# ch340-usb-serial.net
KiCad netlist of a schematic drawn in Altium Designer
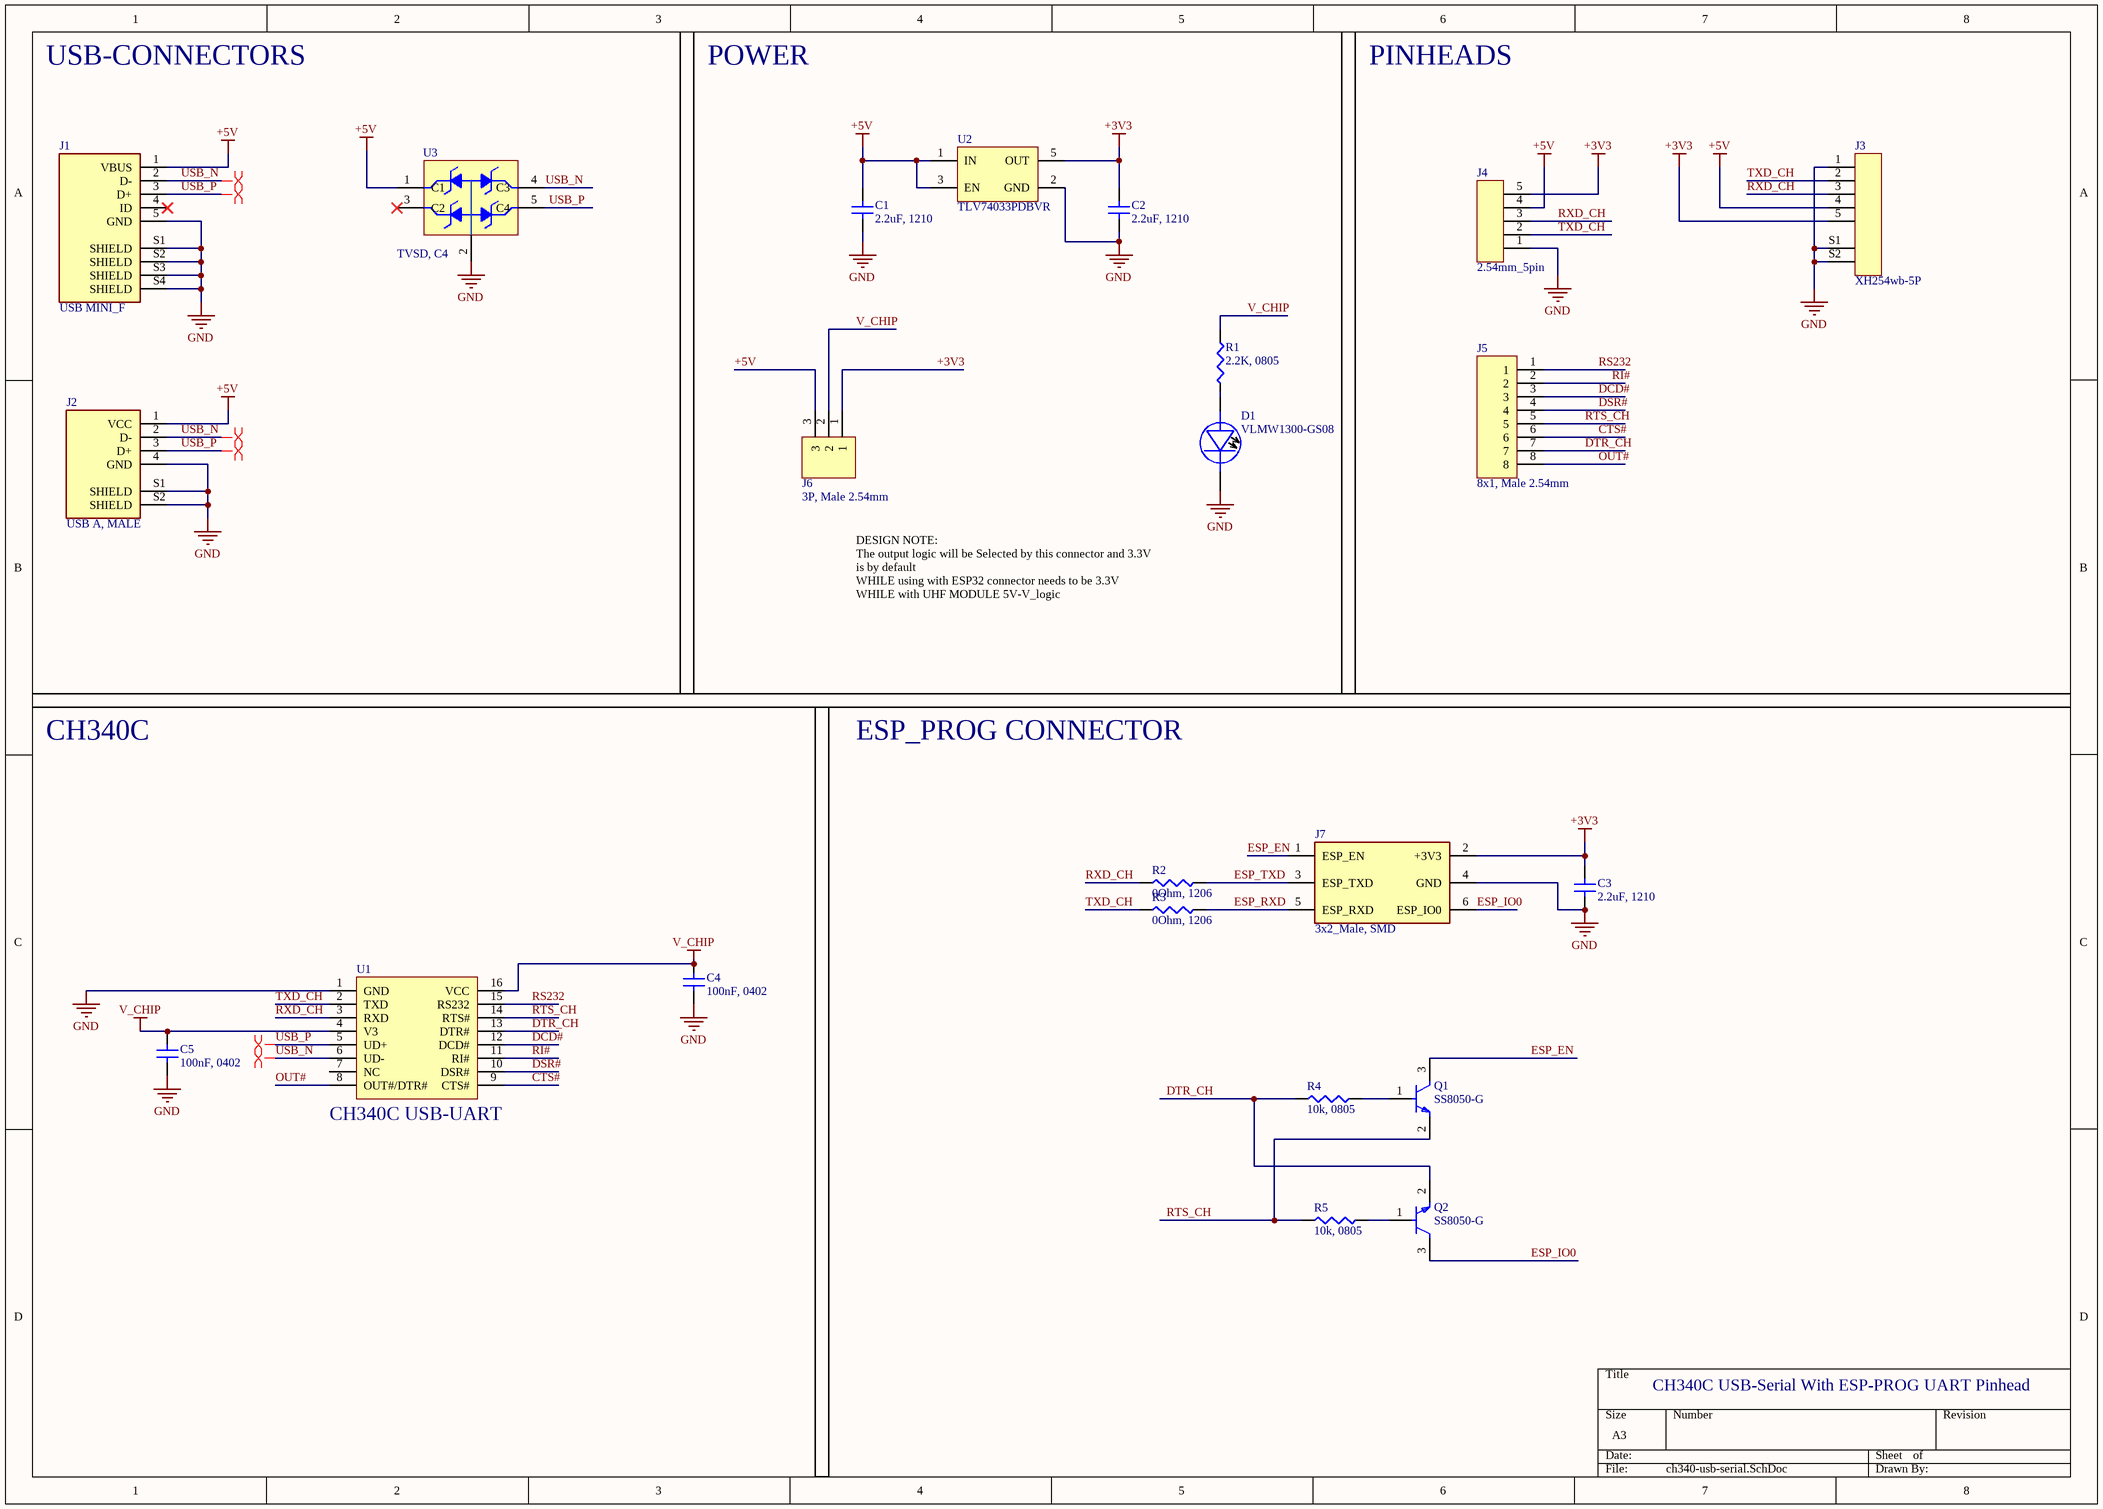
[diagram p0: ch340-usb-serial.SchDoc]

(export (version "E")
  (design (tool "Eeschema 10.0.6"))
  (components
    (comp (ref "C1")
      (value "2.2uF, 1210")
      (footprint "CAP_1210")
      (description "CAP CER 2.2UF 100V X7R 1210")
      (fields
        (field (name "MANUFACTURER") "Samsung")
        (field (name "MANUFACTURER PART NUMBER") "CL32B225KCJSNNE")
      )
      (libsource (lib "Schlib") (part "CL32B225KCJSNNE"))
    )
    (comp (ref "C2")
      (value "2.2uF, 1210")
      (footprint "CAP_1210")
      (description "CAP CER 2.2UF 100V X7R 1210")
      (fields
        (field (name "MANUFACTURER") "Samsung")
        (field (name "MANUFACTURER PART NUMBER") "CL32B225KCJSNNE")
      )
      (libsource (lib "Schlib") (part "CL32B225KCJSNNE"))
    )
    (comp (ref "C3")
      (value "2.2uF, 1210")
      (footprint "CAP_1210")
      (description "CAP CER 2.2UF 100V X7R 1210")
      (fields
        (field (name "MANUFACTURER") "Samsung")
        (field (name "MANUFACTURER PART NUMBER") "CL32B225KCJSNNE")
      )
      (libsource (lib "Schlib") (part "CL32B225KCJSNNE"))
    )
    (comp (ref "C4")
      (value "100nF, 0402")
      (footprint "CAP_0402")
      (description "0.1 µF ±10% 50V Ceramic Capacitor X7R 0402 (1005 Metric)")
      (fields
        (field (name "MANUFACTURER") "Samsung")
        (field (name "MANUFACTURER PART NUMBER") "CL05B104KB54PNC")
      )
      (libsource (lib "Schlib") (part "CL05B104KB54PNC"))
    )
    (comp (ref "C5")
      (value "100nF, 0402")
      (footprint "CAP_0402")
      (description "0.1 µF ±10% 50V Ceramic Capacitor X7R 0402 (1005 Metric)")
      (fields
        (field (name "MANUFACTURER") "Samsung")
        (field (name "MANUFACTURER PART NUMBER") "CL05B104KB54PNC")
      )
      (libsource (lib "Schlib") (part "CL05B104KB54PNC"))
    )
    (comp (ref "D1")
      (value "VLMW1300-GS08")
      (footprint "LED_0603")
      (description "LED COOL WHITE 0603 SMD")
      (fields (field (name "MANUFACTURER") "Vishay Semiconductors"))
      (libsource (lib "Schlib") (part "VLMW1300-GS08"))
    )
    (comp (ref "J1")
      (value "USB MINI_F")
      (footprint "USB_B_Female")
      (description "MINI USB B TYPE RECEPTACLE 5POS")
      (fields
        (field (name "MANUFACTURER") "Amphenol")
        (field (name "MANUFACTURER PART NUMBER") "GMSB0532112YEU")
      )
      (libsource (lib "Schlib") (part "GMSB0532112YEU"))
    )
    (comp (ref "J2")
      (value "USB A, MALE")
      (footprint "USB_A_MALE")
      (description "CONN PLUG USB2.0 TYPEA 4P SMD RA")
      (fields (field (name "MANUFACTURER") "Molex") (field (name "MANUFACTURER PART NUMBER") "0480372200"))
      (libsource (lib "Schlib") (part "0480372200"))
    )
    (comp (ref "J3")
      (value "XH254wb-5P")
      (footprint "5PIN_Header_Connectotor")
      (description "SMT SMD Horizontal Socket Male Header Connector")
      (libsource (lib "Schlib") (part "XH254wb-5P"))
    )
    (comp (ref "J4")
      (value "2.54mm_5pin")
      (footprint "5x1P_Male_2.54")
      (description "CONN HEADER VERT 5POS 2.54MM")
      (libsource (lib "Schlib") (part "2.54mm_5pin"))
    )
    (comp (ref "J5")
      (value "8x1, Male 2.54mm")
      (footprint "8x1P_Male_2.54")
      (description "CONN HEADER VERT 8POS 2.54MM")
      (fields
        (field (name "MANUFACTURER") "Wurth Electronics")
        (field (name "MANUFACTURER PART NUMBER") "61300811121")
      )
      (libsource (lib "Schlib") (part "61300811121"))
    )
    (comp (ref "J6")
      (value "3P, Male 2.54mm")
      (footprint "3x1P_Male_2.54")
      (description "CONN HEADER VERT 3POS 2.54MM")
      (fields
        (field (name "MANUFACTURER") "Wurth Electronics")
        (field (name "MANUFACTURER PART NUMBER") "61300311121")
      )
      (libsource (lib "Schlib") (part "61300311121"))
    )
    (comp (ref "J7")
      (value "3x2_Male, SMD")
      (footprint "3x2P_Male_SMD_1.27")
      (description "CONN HEADER SMD 6POS 1.27MM")
      (fields
        (field (name "MANUFACTURER") "Amphenol Communications Solutions")
        (field (name "MANUFACTURER PART NUMBER") "20021121-00006C4LF")
      )
      (libsource (lib "Schlib") (part "20021121-00006C4LF"))
    )
    (comp (ref "Q1")
      (value "SS8050-G")
      (footprint "FP-SS8050-G-IPC_B")
      (description "TRANS NPN 25V 1.5A SOT23-3")
      (fields (field (name "MANUFACTURER") "Comchip") (field (name "LCSC PART NUMBER") "C164886"))
      (libsource (lib "Schlib") (part "SS8050-G"))
    )
    (comp (ref "Q2")
      (value "SS8050-G")
      (footprint "FP-SS8050-G-IPC_B")
      (description "TRANS NPN 25V 1.5A SOT23-3")
      (fields (field (name "MANUFACTURER") "Comchip") (field (name "LCSC PART NUMBER") "C164886"))
      (libsource (lib "Schlib") (part "SS8050-G"))
    )
    (comp (ref "R1")
      (value "2.2K, 0805")
      (footprint "RES_0805")
      (description "RES SMD 2.2K OHM 1% 1/8W 0805")
      (fields
        (field (name "MANUFACTURER") "Vishay Dale")
        (field (name "MANUFACTURER PART NUMBER") "CRCW08052K20FKEC")
      )
      (libsource (lib "Schlib") (part "CRCW08052K20FKEC"))
    )
    (comp (ref "R2")
      (value "0Ohm, 1206")
      (footprint "RES_1206")
      (description "RES 0 OHM JUMPER 1/4W 1206")
      (fields
        (field (name "MANUFACTURER") "Yageo")
        (field (name "MANUFACTURER PART NUMBER") "RC1206JR-070RL")
      )
      (libsource (lib "Schlib") (part "RC1206JR-070RL"))
    )
    (comp (ref "R3")
      (value "0Ohm, 1206")
      (footprint "RES_1206")
      (description "RES 0 OHM JUMPER 1/4W 1206")
      (fields
        (field (name "MANUFACTURER") "Yageo")
        (field (name "MANUFACTURER PART NUMBER") "RC1206JR-070RL")
      )
      (libsource (lib "Schlib") (part "RC1206JR-070RL"))
    )
    (comp (ref "R4")
      (value "10k, 0805")
      (footprint "RES_0805")
      (description "RES 10K OHM 1% 1/8W 0805")
      (fields
        (field (name "MANUFACTURER") "Yageo")
        (field (name "MANUFACTURER PART NUMBER") "RC0805FR-0710KL")
      )
      (libsource (lib "Schlib") (part "RC0805FR-0710KL"))
    )
    (comp (ref "R5")
      (value "10k, 0805")
      (footprint "RES_0805")
      (description "RES 10K OHM 1% 1/8W 0805")
      (fields
        (field (name "MANUFACTURER") "Yageo")
        (field (name "MANUFACTURER PART NUMBER") "RC0805FR-0710KL")
      )
      (libsource (lib "Schlib") (part "RC0805FR-0710KL"))
    )
    (comp (ref "U1")
      (value "USB-UART")
      (footprint "SOP16")
      (description "SOP-16 USB to UART Converters")
      (libsource (lib "Schlib") (part "CH340C"))
    )
    (comp (ref "U2")
      (value "TLV74033PDBVR")
      (footprint "SOT95P280X145-5N")
      (description "IC REG LINEAR 3.3V 300MA SOT23-5")
      (libsource (lib "Schlib") (part "TLV74033PDBVR"))
    )
    (comp (ref "U3")
      (value "TVSD, C4")
      (footprint "SOT353")
      (description "TVS Quad Common Anode 5.6V 200mW 5-Pin SOT-353 Embossed T/R")
      (fields
        (field (name "MANUFACTURER") "Toshiba")
        (field (name "MANUFACTURER PART NUMBER") "DF5A5.6FUTE85LF")
      )
      (libsource (lib "Schlib") (part "DF5A5.6FUTE85LF"))
    )
  )
  (nets
    (net (code "1") (name "+3V3") (class "Default")
      (node (ref "C2") (pin "1") (pinfunction "1_1") (pintype "passive"))
      (node (ref "C3") (pin "1") (pinfunction "1_1") (pintype "passive"))
      (node (ref "J3") (pin "5") (pintype "passive"))
      (node (ref "J4") (pin "5") (pintype "passive"))
      (node (ref "J6") (pin "1") (pinfunction "1_1") (pintype "passive"))
      (node (ref "J7") (pin "2") (pinfunction "+3V3_2") (pintype "passive"))
      (node (ref "U2") (pin "5") (pinfunction "OUT_5") (pintype "passive"))
    )
    (net (code "2") (name "+5V") (class "Default")
      (node (ref "C1") (pin "1") (pinfunction "1_1") (pintype "passive"))
      (node (ref "J1") (pin "1") (pinfunction "VBUS_1") (pintype "power_in"))
      (node (ref "J2") (pin "1") (pinfunction "VCC_1") (pintype "power_in"))
      (node (ref "J3") (pin "4") (pintype "passive"))
      (node (ref "J4") (pin "4") (pintype "passive"))
      (node (ref "J6") (pin "3") (pinfunction "3_3") (pintype "passive"))
      (node (ref "U2") (pin "1") (pinfunction "IN_1") (pintype "passive"))
      (node (ref "U2") (pin "3") (pinfunction "EN_3") (pintype "passive"))
      (node (ref "U3") (pin "1") (pinfunction "C1_1") (pintype "passive"))
    )
    (net (code "3") (name "/CTS#") (class "Default")
      (node (ref "J5") (pin "6") (pinfunction "6_6") (pintype "passive"))
      (node (ref "U1") (pin "9") (pinfunction "CTS#_9") (pintype "passive"))
    )
    (net (code "4") (name "/DCD#") (class "Default")
      (node (ref "J5") (pin "3") (pinfunction "3_3") (pintype "passive"))
      (node (ref "U1") (pin "12") (pinfunction "DCD#_12") (pintype "passive"))
    )
    (net (code "5") (name "/DSR#") (class "Default")
      (node (ref "J5") (pin "4") (pinfunction "4_4") (pintype "passive"))
      (node (ref "U1") (pin "10") (pinfunction "DSR#_10") (pintype "passive"))
    )
    (net (code "6") (name "/DTR_CH") (class "Default")
      (node (ref "J5") (pin "7") (pinfunction "7_7") (pintype "passive"))
      (node (ref "Q2") (pin "2") (pinfunction "E_2") (pintype "passive"))
      (node (ref "R4") (pin "1") (pinfunction "1_1") (pintype "passive"))
      (node (ref "U1") (pin "13") (pinfunction "DTR#_13") (pintype "passive"))
    )
    (net (code "7") (name "/ESP_EN") (class "Default")
      (node (ref "J7") (pin "1") (pinfunction "ESP_EN_1") (pintype "passive"))
      (node (ref "Q1") (pin "3") (pinfunction "C_3") (pintype "passive"))
    )
    (net (code "8") (name "/ESP_IO0") (class "Default")
      (node (ref "J7") (pin "6") (pinfunction "ESP_IO0_6") (pintype "passive"))
      (node (ref "Q2") (pin "3") (pinfunction "C_3") (pintype "passive"))
    )
    (net (code "9") (name "/ESP_RXD") (class "Default")
      (node (ref "J7") (pin "5") (pinfunction "ESP_RXD_5") (pintype "passive"))
      (node (ref "R3") (pin "2") (pinfunction "2_2") (pintype "passive"))
    )
    (net (code "10") (name "/ESP_TXD") (class "Default")
      (node (ref "J7") (pin "3") (pinfunction "ESP_TXD_3") (pintype "passive"))
      (node (ref "R2") (pin "2") (pinfunction "2_2") (pintype "passive"))
    )
    (net (code "11") (name "/OUT#") (class "Default")
      (node (ref "J5") (pin "8") (pinfunction "8_8") (pintype "passive"))
      (node (ref "U1") (pin "8") (pinfunction "OUT#/DTR#_8") (pintype "passive"))
    )
    (net (code "12") (name "/RI#") (class "Default")
      (node (ref "J5") (pin "2") (pinfunction "2_2") (pintype "passive"))
      (node (ref "U1") (pin "11") (pinfunction "RI#_11") (pintype "passive"))
    )
    (net (code "13") (name "/RS232") (class "Default")
      (node (ref "J5") (pin "1") (pinfunction "1_1") (pintype "passive"))
      (node (ref "U1") (pin "15") (pinfunction "RS232_15") (pintype "passive"))
    )
    (net (code "14") (name "/RTS_CH") (class "Default")
      (node (ref "J5") (pin "5") (pinfunction "5_5") (pintype "passive"))
      (node (ref "Q1") (pin "2") (pinfunction "E_2") (pintype "passive"))
      (node (ref "R5") (pin "1") (pinfunction "1_1") (pintype "passive"))
      (node (ref "U1") (pin "14") (pinfunction "RTS#_14") (pintype "passive"))
    )
    (net (code "15") (name "/RXD_CH") (class "Default")
      (node (ref "J3") (pin "3") (pintype "passive"))
      (node (ref "J4") (pin "3") (pintype "passive"))
      (node (ref "R2") (pin "1") (pinfunction "1_1") (pintype "passive"))
      (node (ref "U1") (pin "3") (pinfunction "RXD_3") (pintype "passive"))
    )
    (net (code "16") (name "/TXD_CH") (class "Default")
      (node (ref "J3") (pin "2") (pintype "passive"))
      (node (ref "J4") (pin "2") (pintype "passive"))
      (node (ref "R3") (pin "1") (pinfunction "1_1") (pintype "passive"))
      (node (ref "U1") (pin "2") (pinfunction "TXD_2") (pintype "passive"))
    )
    (net (code "17") (name "/USB_N") (class "Default")
      (node (ref "J1") (pin "2") (pinfunction "D-_2") (pintype "passive"))
      (node (ref "J2") (pin "2") (pinfunction "D-_2") (pintype "passive"))
      (node (ref "U1") (pin "6") (pinfunction "UD-_6") (pintype "passive"))
      (node (ref "U3") (pin "4") (pinfunction "C3_4") (pintype "passive"))
    )
    (net (code "18") (name "/USB_P") (class "Default")
      (node (ref "J1") (pin "3") (pinfunction "D+_3") (pintype "passive"))
      (node (ref "J2") (pin "3") (pinfunction "D+_3") (pintype "passive"))
      (node (ref "U1") (pin "5") (pinfunction "UD+_5") (pintype "passive"))
      (node (ref "U3") (pin "5") (pinfunction "C4_5") (pintype "passive"))
    )
    (net (code "19") (name "GND") (class "Default")
      (node (ref "C1") (pin "2") (pinfunction "2_2") (pintype "passive"))
      (node (ref "C2") (pin "2") (pinfunction "2_2") (pintype "passive"))
      (node (ref "C3") (pin "2") (pinfunction "2_2") (pintype "passive"))
      (node (ref "C4") (pin "1") (pinfunction "1_1") (pintype "passive"))
      (node (ref "C5") (pin "1") (pinfunction "1_1") (pintype "passive"))
      (node (ref "D1") (pin "K-") (pinfunction "2_K-") (pintype "passive"))
      (node (ref "J1") (pin "5") (pinfunction "GND_5") (pintype "power_in"))
      (node (ref "J1") (pin "S1") (pinfunction "SHIELD_S1") (pintype "passive"))
      (node (ref "J1") (pin "S2") (pinfunction "SHIELD_S2") (pintype "passive"))
      (node (ref "J1") (pin "S3") (pinfunction "SHIELD_S3") (pintype "passive"))
      (node (ref "J1") (pin "S4") (pinfunction "SHIELD_S4") (pintype "passive"))
      (node (ref "J2") (pin "4") (pinfunction "GND_4") (pintype "power_in"))
      (node (ref "J2") (pin "S1") (pinfunction "SHIELD_S1") (pintype "passive"))
      (node (ref "J2") (pin "S2") (pinfunction "SHIELD_S2") (pintype "passive"))
      (node (ref "J3") (pin "1") (pintype "passive"))
      (node (ref "J3") (pin "S1") (pintype "passive"))
      (node (ref "J3") (pin "S2") (pintype "passive"))
      (node (ref "J4") (pin "1") (pintype "passive"))
      (node (ref "J7") (pin "4") (pinfunction "GND_4") (pintype "passive"))
      (node (ref "U1") (pin "1") (pinfunction "GND_1") (pintype "passive"))
      (node (ref "U2") (pin "2") (pinfunction "GND_2") (pintype "passive"))
      (node (ref "U3") (pin "2") (pinfunction "A_2") (pintype "passive"))
    )
    (net (code "20") (name "Net-(D1-1)") (class "Default")
      (node (ref "D1") (pin "A+") (pinfunction "1_A+") (pintype "passive"))
      (node (ref "R1") (pin "1") (pinfunction "1_1") (pintype "passive"))
    )
    (net (code "21") (name "Net-(Q1-B)") (class "Default")
      (node (ref "Q1") (pin "1") (pinfunction "B_1") (pintype "passive"))
      (node (ref "R4") (pin "2") (pinfunction "2_2") (pintype "passive"))
    )
    (net (code "22") (name "Net-(Q2-B)") (class "Default")
      (node (ref "Q2") (pin "1") (pinfunction "B_1") (pintype "passive"))
      (node (ref "R5") (pin "2") (pinfunction "2_2") (pintype "passive"))
    )
    (net (code "23") (name "V_CHIP") (class "Default")
      (node (ref "C4") (pin "2") (pinfunction "2_2") (pintype "passive"))
      (node (ref "C5") (pin "2") (pinfunction "2_2") (pintype "passive"))
      (node (ref "J6") (pin "2") (pinfunction "2_2") (pintype "passive"))
      (node (ref "R1") (pin "2") (pinfunction "2_2") (pintype "passive"))
      (node (ref "U1") (pin "16") (pinfunction "VCC_16") (pintype "passive"))
      (node (ref "U1") (pin "4") (pinfunction "V3_4") (pintype "passive"))
    )
    (net (code "24") (name "unconnected-(J1-ID-Pad4)") (class "Default")
      (node (ref "J1") (pin "4") (pinfunction "ID_4") (pintype "passive+no_connect"))
    )
    (net (code "25") (name "unconnected-(U1-NC-Pad7)") (class "Default")
      (node (ref "U1") (pin "7") (pinfunction "NC_7") (pintype "passive"))
    )
    (net (code "26") (name "unconnected-(U3-C2-Pad3)") (class "Default")
      (node (ref "U3") (pin "3") (pinfunction "C2_3") (pintype "passive+no_connect"))
    )
  )
)
